# HIVE_SIGHT_MISC.net
KiCad netlist of a schematic drawn in Altium Designer
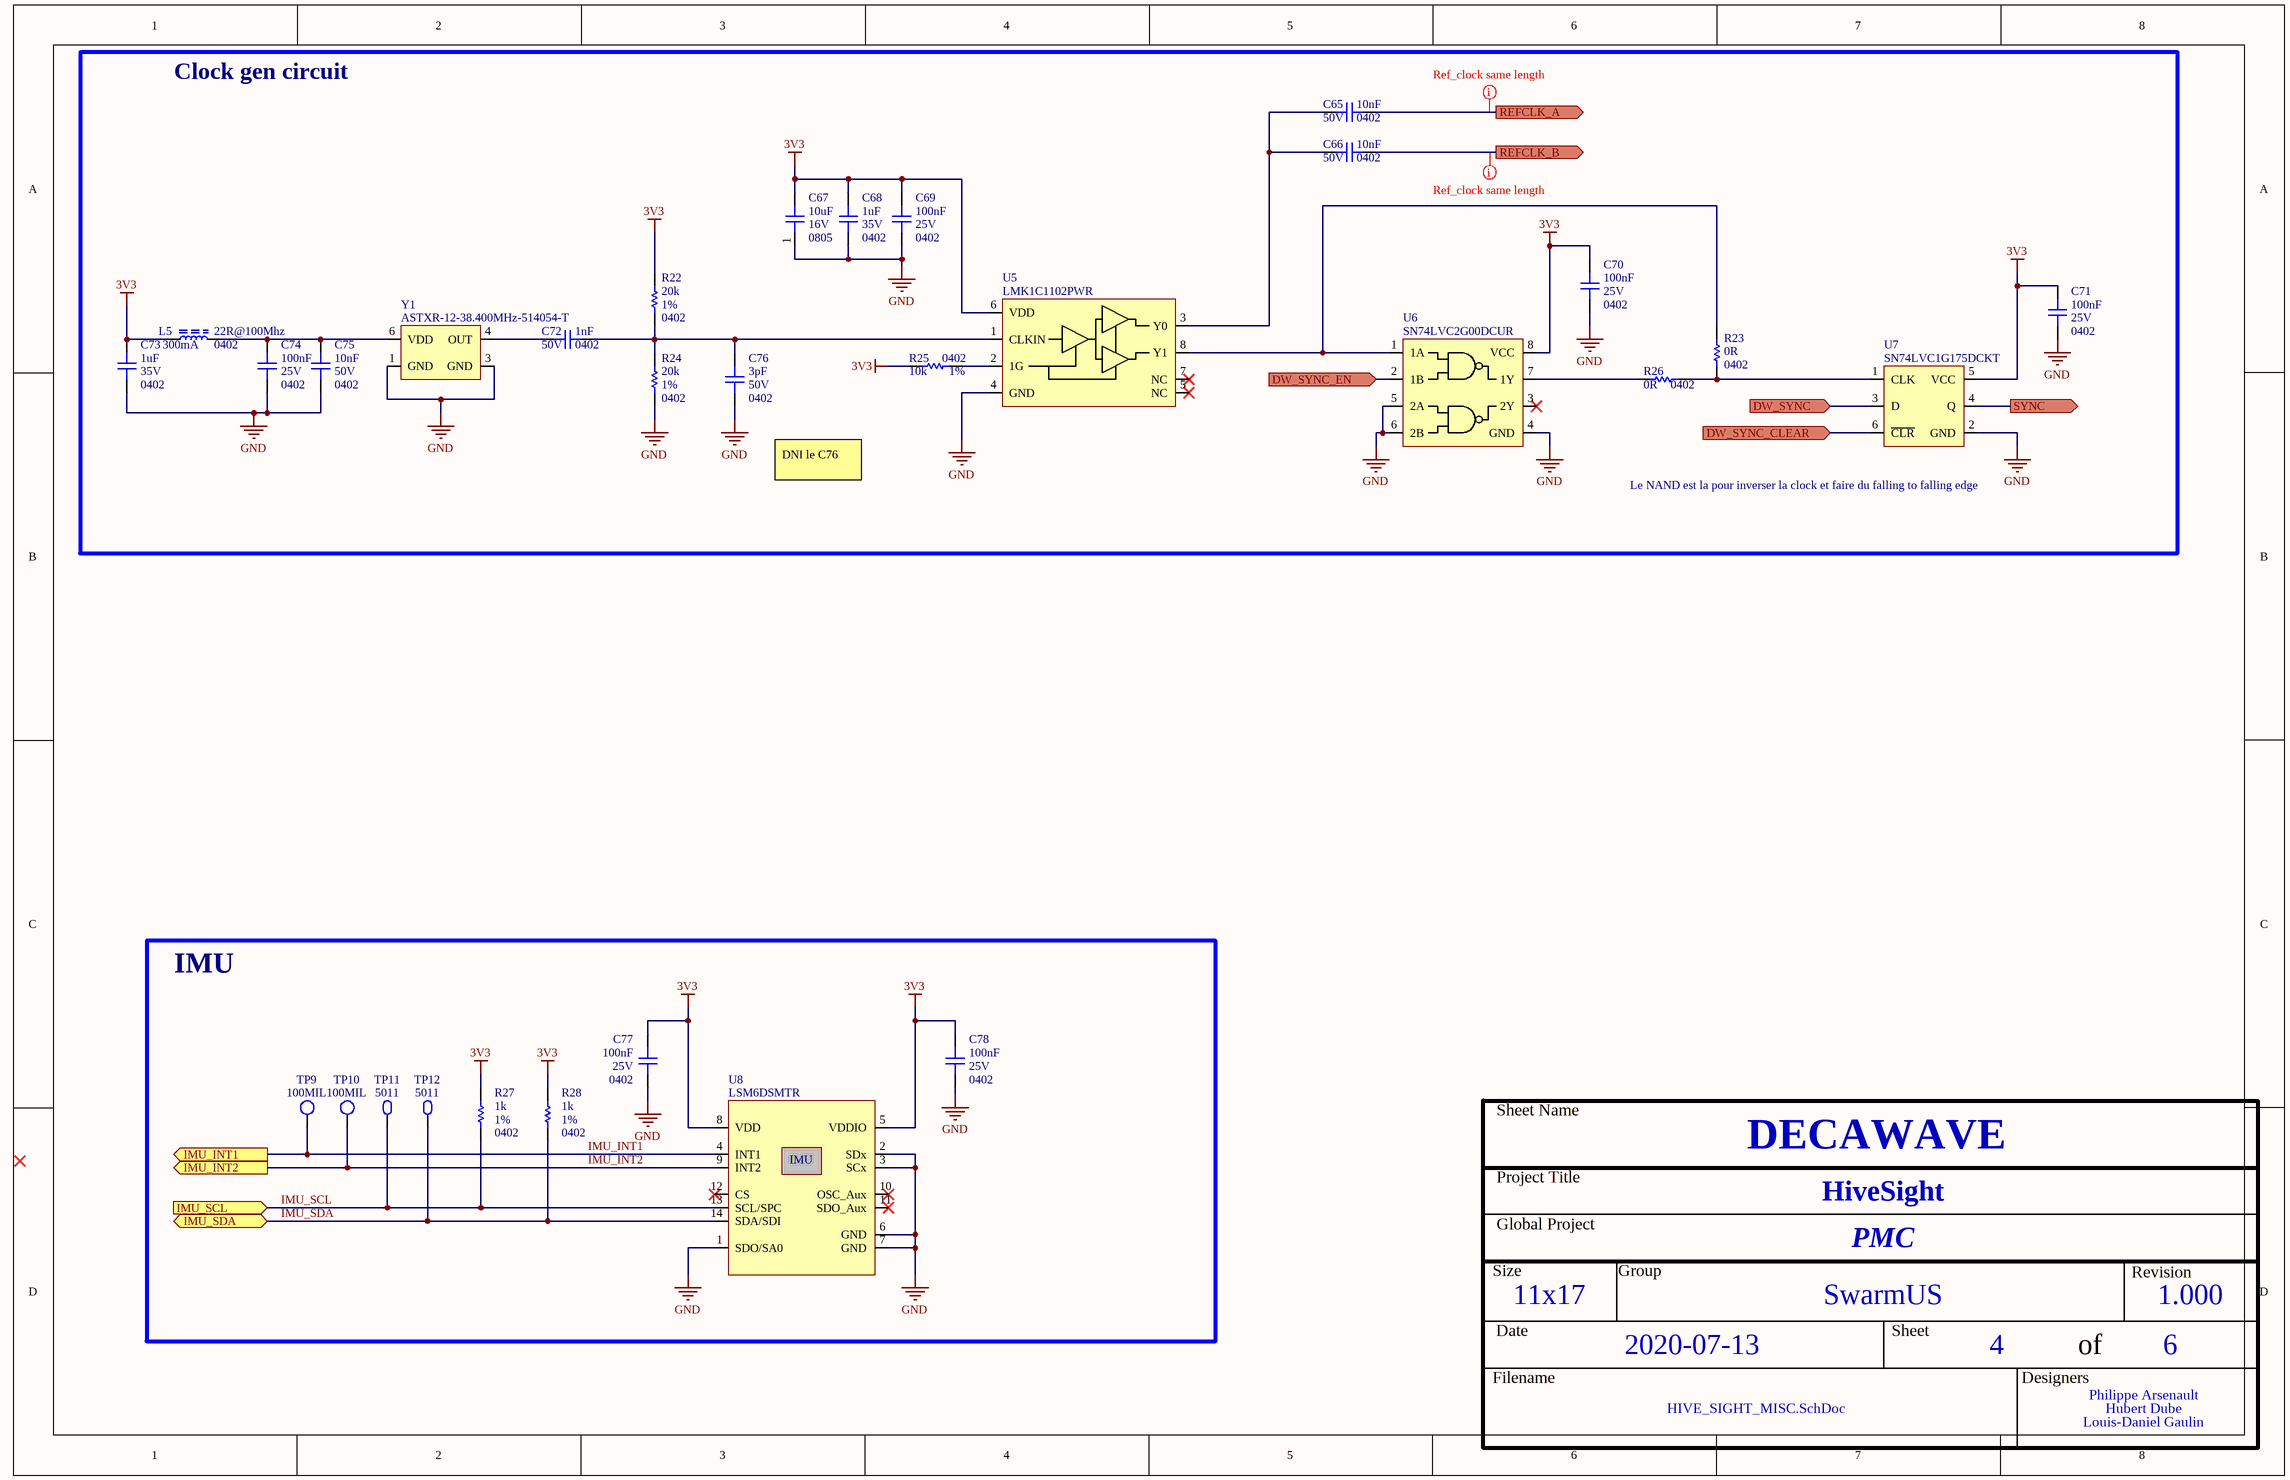
[diagram p0: HIVE_SIGHT_MISC.SchDoc]

(export (version "E")
  (design (tool "Eeschema 10.0.6"))
  (components
    (comp (ref "C65")
      (value "10nF")
      (footprint "GRAMS_MASTER_LIB_PCB:CAP_CER_0402")
      (description "CAP - CER 10nF ±10% 50V X7R - 0402")
      (fields
        (field (name "TOLERANCE") "10%")
        (field (name "PACKAGE") "0402")
        (field (name "VOLTAGE RATING") "50V")
        (field (name "Comment") "CL05B103KB5NFNC")
        (field (name "CREATEDBY/DATE") "Keven Deslandes - 2018/11/20")
        (field (name "VERIFIEDBY") "Nicolas Roy - 2018/12/11")
      )
      (libsource (lib "GRAMS_MASTER_LIB_SCH") (part "CAP_CER_CL05B103KB5NFNC"))
    )
    (comp (ref "C66")
      (value "10nF")
      (footprint "GRAMS_MASTER_LIB_PCB:CAP_CER_0402")
      (description "CAP - CER 10nF ±10% 50V X7R - 0402")
      (fields
        (field (name "TOLERANCE") "10%")
        (field (name "PACKAGE") "0402")
        (field (name "VOLTAGE RATING") "50V")
        (field (name "Comment") "CL05B103KB5NFNC")
        (field (name "CREATEDBY/DATE") "Keven Deslandes - 2018/11/20")
        (field (name "VERIFIEDBY") "Nicolas Roy - 2018/12/11")
      )
      (libsource (lib "GRAMS_MASTER_LIB_SCH") (part "CAP_CER_CL05B103KB5NFNC"))
    )
    (comp (ref "C67")
      (value "10uF")
      (footprint "CAP_CER_0805")
      (description "CAP - CER 10UF 10% 16V X5R - 0805")
      (fields
        (field (name "TOLERANCE") "10%")
        (field (name "PACKAGE") "0805")
        (field (name "VOLTAGE RATING") "16V")
        (field (name "Comment") "GRM21BR61C106KE15K")
        (field (name "CREATEDBY/DATE") "Caroline Paulin / 8 août 2018")
        (field (name "VERIFIEDBY") "Nicolas V. (2019-01-22)")
      )
      (libsource (lib "GRAMS_MASTER_LIB") (part "CAP_CER_GRM21BR61C106KE15K"))
    )
    (comp (ref "C68")
      (value "1uF")
      (footprint "GRAMS_MASTER_LIB_PCB:CAP_CER_0402")
      (description "CAP - CER 1uF 10% 35V X5R - 0402")
      (fields
        (field (name "TOLERANCE") "10%")
        (field (name "PACKAGE") "0402")
        (field (name "VOLTAGE RATING") "35V")
        (field (name "Comment") "CL05A105KL5NRNC")
        (field (name "CREATEDBY/DATE") "Nicolas Roy 2018-10-03")
        (field (name "VERIFIEDBY") "Caroline Paulin - 18 janv 2019")
      )
      (libsource (lib "GRAMS_MASTER_LIB_SCH") (part "CAP_CER_CL05A105KL5NRNC"))
    )
    (comp (ref "C69")
      (value "100nF")
      (footprint "GRAMS_MASTER_LIB_PCB:CAP_CER_0402")
      (description "CAP - CER 0.1µF 10% 25V X7R - 0402")
      (fields
        (field (name "TOLERANCE") "10%")
        (field (name "PACKAGE") "0402")
        (field (name "VOLTAGE RATING") "25V")
        (field (name "Comment") "CGA2B3X7R1E104K050BB")
        (field (name "CREATEDBY/DATE") "Nicolas Roy 2018-11-07")
        (field (name "VERIFIEDBY") "Nicolas V. (2019-01-22)")
      )
      (libsource (lib "GRAMS_MASTER_LIB_SCH") (part "CAP_CER_CGA2B3X7R1E104K050BB"))
    )
    (comp (ref "C70")
      (value "100nF")
      (footprint "GRAMS_MASTER_LIB_PCB:CAP_CER_0402")
      (description "CAP - CER 0.1µF 10% 25V X7R - 0402")
      (fields
        (field (name "TOLERANCE") "10%")
        (field (name "PACKAGE") "0402")
        (field (name "VOLTAGE RATING") "25V")
        (field (name "Comment") "CGA2B3X7R1E104K050BB")
        (field (name "CREATEDBY/DATE") "Nicolas Roy 2018-11-07")
        (field (name "VERIFIEDBY") "Nicolas V. (2019-01-22)")
      )
      (libsource (lib "GRAMS_MASTER_LIB_SCH") (part "CAP_CER_CGA2B3X7R1E104K050BB"))
    )
    (comp (ref "C71")
      (value "100nF")
      (footprint "GRAMS_MASTER_LIB_PCB:CAP_CER_0402")
      (description "CAP - CER 0.1µF 10% 25V X7R - 0402")
      (fields
        (field (name "TOLERANCE") "10%")
        (field (name "PACKAGE") "0402")
        (field (name "VOLTAGE RATING") "25V")
        (field (name "Comment") "CGA2B3X7R1E104K050BB")
        (field (name "CREATEDBY/DATE") "Nicolas Roy 2018-11-07")
        (field (name "VERIFIEDBY") "Nicolas V. (2019-01-22)")
      )
      (libsource (lib "GRAMS_MASTER_LIB_SCH") (part "CAP_CER_CGA2B3X7R1E104K050BB"))
    )
    (comp (ref "C72")
      (value "1nF")
      (footprint "CAP_CER_0402")
      (description "CAP - CER 1nF 10% 50V X7R - 0402")
      (fields
        (field (name "TOLERANCE") "10%")
        (field (name "PACKAGE") "0402")
        (field (name "VOLTAGE RATING") "50V")
        (field (name "Comment") "CC0402KRX7R9BB102")
        (field (name "CREATEDBY/DATE") "Jonathan Bouchard 2019-04-06")
        (field (name "VERIFIEDBY") "Nicolas V. (2019-04-30)")
      )
      (libsource (lib "GRAMS_MASTER_LIB_SCH") (part "CAP_CER_CC0402KRX7R9BB102"))
    )
    (comp (ref "C73")
      (value "1uF")
      (footprint "GRAMS_MASTER_LIB_PCB:CAP_CER_0402")
      (description "CAP - CER 1uF 10% 35V X5R - 0402")
      (fields
        (field (name "TOLERANCE") "10%")
        (field (name "PACKAGE") "0402")
        (field (name "VOLTAGE RATING") "35V")
        (field (name "Comment") "CL05A105KL5NRNC")
        (field (name "CREATEDBY/DATE") "Nicolas Roy 2018-10-03")
        (field (name "VERIFIEDBY") "Caroline Paulin - 18 janv 2019")
      )
      (libsource (lib "GRAMS_MASTER_LIB_SCH") (part "CAP_CER_CL05A105KL5NRNC"))
    )
    (comp (ref "C74")
      (value "100nF")
      (footprint "GRAMS_MASTER_LIB_PCB:CAP_CER_0402")
      (description "CAP - CER 0.1µF 10% 25V X7R - 0402")
      (fields
        (field (name "TOLERANCE") "10%")
        (field (name "PACKAGE") "0402")
        (field (name "VOLTAGE RATING") "25V")
        (field (name "Comment") "CGA2B3X7R1E104K050BB")
        (field (name "CREATEDBY/DATE") "Nicolas Roy 2018-11-07")
        (field (name "VERIFIEDBY") "Nicolas V. (2019-01-22)")
      )
      (libsource (lib "GRAMS_MASTER_LIB_SCH") (part "CAP_CER_CGA2B3X7R1E104K050BB"))
    )
    (comp (ref "C75")
      (value "10nF")
      (footprint "GRAMS_MASTER_LIB_PCB:CAP_CER_0402")
      (description "CAP - CER 10nF ±10% 50V X7R - 0402")
      (fields
        (field (name "TOLERANCE") "10%")
        (field (name "PACKAGE") "0402")
        (field (name "VOLTAGE RATING") "50V")
        (field (name "Comment") "CL05B103KB5NFNC")
        (field (name "CREATEDBY/DATE") "Keven Deslandes - 2018/11/20")
        (field (name "VERIFIEDBY") "Nicolas Roy - 2018/12/11")
      )
      (libsource (lib "GRAMS_MASTER_LIB_SCH") (part "CAP_CER_CL05B103KB5NFNC"))
    )
    (comp (ref "C76")
      (value "3pF")
      (footprint "CAP_CER_0402")
      (description "CAP - CER 3pF 50V ±0.25pF C0G, NP0 - 0402")
      (fields
        (field (name "TOLERANCE") "±0.25pF")
        (field (name "PACKAGE") "0402")
        (field (name "VOLTAGE RATING") "50V")
        (field (name "Comment") "CC0402CRNPO9BN3R0")
        (field (name "CREATEDBY/DATE") "Philippe Arsenault/ 2020-07-24")
        (field (name "VERIFIEDBY") "Louis-Daniel Gaulin / 2020-07-29")
      )
      (libsource (lib "SWARMUS_LIB") (part "CAP_CER_CC0402CRNPO9BN3R0"))
    )
    (comp (ref "C77")
      (value "100nF")
      (footprint "GRAMS_MASTER_LIB_PCB:CAP_CER_0402")
      (description "CAP - CER 0.1µF 10% 25V X7R - 0402")
      (fields
        (field (name "TOLERANCE") "10%")
        (field (name "PACKAGE") "0402")
        (field (name "VOLTAGE RATING") "25V")
        (field (name "Comment") "CGA2B3X7R1E104K050BB")
        (field (name "CREATEDBY/DATE") "Nicolas Roy 2018-11-07")
        (field (name "VERIFIEDBY") "Nicolas V. (2019-01-22)")
      )
      (libsource (lib "GRAMS_MASTER_LIB_SCH") (part "CAP_CER_CGA2B3X7R1E104K050BB"))
    )
    (comp (ref "C78")
      (value "100nF")
      (footprint "GRAMS_MASTER_LIB_PCB:CAP_CER_0402")
      (description "CAP - CER 0.1µF 10% 25V X7R - 0402")
      (fields
        (field (name "TOLERANCE") "10%")
        (field (name "PACKAGE") "0402")
        (field (name "VOLTAGE RATING") "25V")
        (field (name "Comment") "CGA2B3X7R1E104K050BB")
        (field (name "CREATEDBY/DATE") "Nicolas Roy 2018-11-07")
        (field (name "VERIFIEDBY") "Nicolas V. (2019-01-22)")
      )
      (libsource (lib "GRAMS_MASTER_LIB_SCH") (part "CAP_CER_CGA2B3X7R1E104K050BB"))
    )
    (comp (ref "L5")
      (value "22R@100Mhz")
      (footprint "FER_0402")
      (description "FER - FERRITE BEAD 22 OHM - 0402")
      (fields
        (field (name "CURRENT RATING") "300mA")
        (field (name "PACKAGE") "0402")
        (field (name "Comment") "BLM15BB220SN1D")
        (field (name "CREATEDBY/DATE") "Philippe Arsenault/2020-11-03")
      )
      (libsource (lib "a_Valider_PA") (part "FER_BLM15BB220SN1D"))
    )
    (comp (ref "R22")
      (value "20k")
      (footprint "GRAMS_MASTER_LIB_PCB:RES_0402")
      (description "RES - 20K 1% 1/16W  - 0402")
      (fields
        (field (name "TOLERANCE") "1%")
        (field (name "PACKAGE") "0402")
        (field (name "Comment") "RC0402FR-0720KL")
        (field (name "CREATEDBY/DATE") "Keven Deslandes 2018-10-18")
        (field (name "VERIFIEDBY") "Caroline Paulin - 7 janv 2019")
      )
      (libsource (lib "GRAMS_MASTER_LIB_SCH") (part "RES_RC0402FR-0720KL"))
    )
    (comp (ref "R23")
      (value "0R")
      (footprint "RES_0402")
      (description "RES - 0R 1/16W 1A  - 0402")
      (fields
        (field (name "PACKAGE") "0402")
        (field (name "Comment") "RC0402FR-070RL")
        (field (name "CREATEDBY/DATE") "Keven Deslandes 2018-09-12")
        (field (name "VERIFIEDBY") "Caroline Paulin - 27 fév 2019")
      )
      (libsource (lib "GRAMS_MASTER_LIB") (part "RES_RC0402FR-070RL"))
    )
    (comp (ref "R24")
      (value "20k")
      (footprint "GRAMS_MASTER_LIB_PCB:RES_0402")
      (description "RES - 20K 1% 1/16W  - 0402")
      (fields
        (field (name "TOLERANCE") "1%")
        (field (name "PACKAGE") "0402")
        (field (name "Comment") "RC0402FR-0720KL")
        (field (name "CREATEDBY/DATE") "Keven Deslandes 2018-10-18")
        (field (name "VERIFIEDBY") "Caroline Paulin - 7 janv 2019")
      )
      (libsource (lib "GRAMS_MASTER_LIB_SCH") (part "RES_RC0402FR-0720KL"))
    )
    (comp (ref "R25")
      (value "10k")
      (footprint "GRAMS_MASTER_LIB_PCB:RES_0402")
      (description "RES - 10K OHMS 1% 1/16W - 0402")
      (fields
        (field (name "TOLERANCE") "1%")
        (field (name "PACKAGE") "0402")
        (field (name "Comment") "RC0402FR-0710KL")
        (field (name "CREATEDBY/DATE") "Nicolas V. (2018-11-20)")
        (field (name "VERIFIEDBY") "Nicolas V. (2018-11-20)")
      )
      (libsource (lib "GRAMS_MASTER_LIB_SCH") (part "RES_RC0402FR-0710KL"))
    )
    (comp (ref "R26")
      (value "0R")
      (footprint "RES_0402")
      (description "RES - 0R 1/16W 1A  - 0402")
      (fields
        (field (name "PACKAGE") "0402")
        (field (name "Comment") "RC0402FR-070RL")
        (field (name "CREATEDBY/DATE") "Keven Deslandes 2018-09-12")
        (field (name "VERIFIEDBY") "Caroline Paulin - 27 fév 2019")
      )
      (libsource (lib "GRAMS_MASTER_LIB") (part "RES_RC0402FR-070RL"))
    )
    (comp (ref "R27")
      (value "1k")
      (footprint "GRAMS_MASTER_LIB_PCB:RES_0402")
      (description "RES - 1K OHM 1% 1/16W - 0402")
      (fields
        (field (name "TOLERANCE") "1%")
        (field (name "PACKAGE") "0402")
        (field (name "Comment") "RC0402FR-071KL")
        (field (name "CREATEDBY/DATE") "Jonathan Bouchard 2018-07-05")
        (field (name "VERIFIEDBY") "Arnaud Samson 16-07-18")
      )
      (libsource (lib "GRAMS_MASTER_LIB_SCH") (part "RES_RC0402FR-071KL"))
    )
    (comp (ref "R28")
      (value "1k")
      (footprint "GRAMS_MASTER_LIB_PCB:RES_0402")
      (description "RES - 1K OHM 1% 1/16W - 0402")
      (fields
        (field (name "TOLERANCE") "1%")
        (field (name "PACKAGE") "0402")
        (field (name "Comment") "RC0402FR-071KL")
        (field (name "CREATEDBY/DATE") "Jonathan Bouchard 2018-07-05")
        (field (name "VERIFIEDBY") "Arnaud Samson 16-07-18")
      )
      (libsource (lib "GRAMS_MASTER_LIB_SCH") (part "RES_RC0402FR-071KL"))
    )
    (comp (ref "TP9")
      (value "100MIL")
      (footprint "grams_master_lib_pcb:TPO_TH_ROUND_100MIL")
      (description "TPO - TEST POINT ROUND TH  - 100MIL")
      (fields
        (field (name "CREATEDBY/DATE") "Louis-Daniel Gaulin/ 14/01/2020")
        (field (name "VERIFIEDBY") "C.Paulin - 21/01/2020")
      )
      (libsource (lib "GRAMS_MASTER_LIB_SCH") (part "TPO_TH_ROUND_100MIL"))
    )
    (comp (ref "TP10")
      (value "100MIL")
      (footprint "grams_master_lib_pcb:TPO_TH_ROUND_100MIL")
      (description "TPO - TEST POINT ROUND TH  - 100MIL")
      (fields
        (field (name "CREATEDBY/DATE") "Louis-Daniel Gaulin/ 14/01/2020")
        (field (name "VERIFIEDBY") "C.Paulin - 21/01/2020")
      )
      (libsource (lib "GRAMS_MASTER_LIB_SCH") (part "TPO_TH_ROUND_100MIL"))
    )
    (comp (ref "TP11")
      (value "5011")
      (footprint "TPO_5011")
      (description "TPO - TEST POINT - TH")
      (fields
        (field (name "CREATEDBY/DATE") "Louis-Daniel Gauli / 02-11-2020")
        (field (name "VERIFIEDBY") "Philippe Arsenault/2020-11-06")
      )
      (libsource (lib "SWARMUS_LIB") (part "TPO_5011"))
    )
    (comp (ref "TP12")
      (value "5011")
      (footprint "TPO_5011")
      (description "TPO - TEST POINT - TH")
      (fields
        (field (name "CREATEDBY/DATE") "Louis-Daniel Gauli / 02-11-2020")
        (field (name "VERIFIEDBY") "Philippe Arsenault/2020-11-06")
      )
      (libsource (lib "SWARMUS_LIB") (part "TPO_5011"))
    )
    (comp (ref "U5")
      (value "LMK1C1102PWR")
      (footprint "COM_BUF_LMK1C1102PWR")
      (description "COM - BUF - Clock buffer 3V3, 2V5, 1V8 2 Channel - TSSOP 8")
      (fields
        (field (name "CREATEDBY/DATE") "Philippe Arsenault/20-07-2020")
        (field (name "VERIFIEDBY") "Louis-Daniel Gaulin / 23-07-2020")
      )
      (libsource (lib "SWARMUS_LIB") (part "COM_BUF_LMK1C1102PWR"))
    )
    (comp (ref "U6")
      (value "SN74LVC2G00DCUR")
      (footprint "LOG_NAND_SN74LVC2G00DCUR")
      (description "LOG_NAND - GATE NAND 2CH 2-INP - 8-VSSOP")
      (fields
        (field (name "CREATEDBY/DATE") "Philippe Arsenault/21-07-2020")
        (field (name "VERIFIEDBY") "Louis-Daniel Gaulin / 23-07-2020")
      )
      (libsource (lib "SWARMUS_LIB") (part "LOG_NAND_SN74LVC2G00DCUR"))
    )
    (comp (ref "U7")
      (value "SN74LVC1G175DCKT")
      (footprint "LOG_FLIPFLOP_SN74LVC1G175DCKT")
      (description "LOG_FLIPFLOP - Single D flip-flop with Asynchronous clear - SOT-363")
      (fields
        (field (name "CREATEDBY/DATE") "Philippe Arsenault/21-07-2020")
        (field (name "VERIFIEDBY") "Louis-Daniel Gaulin / 03-10-2020")
      )
      (libsource (lib "SWARMUS_LIB") (part "LOG_FLIPFLOP_SN74LVC1G175DCKT"))
    )
    (comp (ref "U8")
      (value "LSM6DSMTR")
      (footprint "SEN_IMU_LSM6DSMTR")
      (description "SEN_IMU -  ACCEL/GYRO 6 Axis I2C/SPI - 14-VFLGA")
      (fields
        (field (name "CREATEDBY/DATE") "Louis-Daniel Gaulin / 06-10-2020")
        (field (name "VERIFIEDBY") "Philippe Arsenault/2020-11-06")
      )
      (libsource (lib "SWARMUS_LIB") (part "SEN_IMU_LSM6DSMTR"))
    )
    (comp (ref "Y1")
      (value "ASTXR-12-38.400MHz-514054-T")
      (footprint "OSC_ASTXR-12-38.400MHZ-514054-T")
      (fields
        (field (name "CREATEDBY/DATE") "Philippe Arsenault/18-07-2020")
        (field (name "VERIFIEDBY") "Louis-Daniel Gaulin / 03-10-2020")
      )
      (libsource (lib "SWARMUS_LIB") (part "OSC_ASTXR-12-38.400MHz-514054-T"))
    )
  )
  (nets
    (net (code "1") (name "/DW_SYNC") (class "Default")
      (node (ref "U7") (pin "3") (pinfunction "D_3") (pintype "passive"))
    )
    (net (code "2") (name "/DW_SYNC_CLEAR") (class "Default")
      (node (ref "U7") (pin "6") (pinfunction "CLR_6") (pintype "passive"))
    )
    (net (code "3") (name "/DW_SYNC_EN") (class "Default")
      (node (ref "U6") (pin "2") (pinfunction "1B_2") (pintype "passive"))
    )
    (net (code "4") (name "/IMU_INT1") (class "Default")
      (node (ref "TP9") (pin "1") (pinfunction "1_1") (pintype "passive"))
      (node (ref "U8") (pin "4") (pinfunction "INT1_4") (pintype "passive"))
    )
    (net (code "5") (name "/IMU_INT2") (class "Default")
      (node (ref "TP10") (pin "1") (pinfunction "1_1") (pintype "passive"))
      (node (ref "U8") (pin "9") (pinfunction "INT2_9") (pintype "passive"))
    )
    (net (code "6") (name "/IMU_SCL") (class "Default")
      (node (ref "R27") (pin "2") (pinfunction "2_2") (pintype "passive"))
      (node (ref "TP11") (pin "1") (pinfunction "1_1") (pintype "passive"))
      (node (ref "U8") (pin "13") (pinfunction "SCL/SPC_13") (pintype "passive"))
    )
    (net (code "7") (name "/IMU_SDA") (class "Default")
      (node (ref "R28") (pin "2") (pinfunction "2_2") (pintype "passive"))
      (node (ref "TP12") (pin "1") (pinfunction "1_1") (pintype "passive"))
      (node (ref "U8") (pin "14") (pinfunction "SDA/SDI_14") (pintype "passive"))
    )
    (net (code "8") (name "/REFCLK_A") (class "Default")
      (node (ref "C65") (pin "1") (pinfunction "1_1") (pintype "passive"))
    )
    (net (code "9") (name "/REFCLK_B") (class "Default")
      (node (ref "C66") (pin "1") (pinfunction "1_1") (pintype "passive"))
    )
    (net (code "10") (name "/SYNC") (class "Default")
      (node (ref "U7") (pin "4") (pinfunction "Q_4") (pintype "passive"))
    )
    (net (code "11") (name "3V3") (class "Default")
      (node (ref "C67") (pin "2") (pinfunction "2_2") (pintype "passive"))
      (node (ref "C68") (pin "2") (pinfunction "2_2") (pintype "passive"))
      (node (ref "C69") (pin "2") (pinfunction "2_2") (pintype "passive"))
      (node (ref "C70") (pin "2") (pinfunction "2_2") (pintype "passive"))
      (node (ref "C71") (pin "1") (pinfunction "1_1") (pintype "passive"))
      (node (ref "C73") (pin "2") (pinfunction "2_2") (pintype "passive"))
      (node (ref "C77") (pin "1") (pinfunction "1_1") (pintype "passive"))
      (node (ref "C78") (pin "1") (pinfunction "1_1") (pintype "passive"))
      (node (ref "L5") (pin "1") (pinfunction "1_1") (pintype "passive"))
      (node (ref "R22") (pin "2") (pinfunction "2_2") (pintype "passive"))
      (node (ref "R25") (pin "2") (pinfunction "2_2") (pintype "passive"))
      (node (ref "R27") (pin "1") (pinfunction "1_1") (pintype "passive"))
      (node (ref "R28") (pin "1") (pinfunction "1_1") (pintype "passive"))
      (node (ref "U5") (pin "6") (pinfunction "VDD_6") (pintype "passive"))
      (node (ref "U6") (pin "8") (pinfunction "VCC_8") (pintype "passive"))
      (node (ref "U7") (pin "5") (pinfunction "VCC_5") (pintype "passive"))
      (node (ref "U8") (pin "5") (pinfunction "VDDIO_5") (pintype "passive"))
      (node (ref "U8") (pin "8") (pinfunction "VDD_8") (pintype "passive"))
    )
    (net (code "12") (name "GND") (class "Default")
      (node (ref "C67") (pin "1") (pinfunction "1_1") (pintype "passive"))
      (node (ref "C68") (pin "1") (pinfunction "1_1") (pintype "passive"))
      (node (ref "C69") (pin "1") (pinfunction "1_1") (pintype "passive"))
      (node (ref "C70") (pin "1") (pinfunction "1_1") (pintype "passive"))
      (node (ref "C71") (pin "2") (pinfunction "2_2") (pintype "passive"))
      (node (ref "C73") (pin "1") (pinfunction "1_1") (pintype "passive"))
      (node (ref "C74") (pin "1") (pinfunction "1_1") (pintype "passive"))
      (node (ref "C75") (pin "1") (pinfunction "1_1") (pintype "passive"))
      (node (ref "C76") (pin "1") (pinfunction "1_1") (pintype "passive"))
      (node (ref "C77") (pin "2") (pinfunction "2_2") (pintype "passive"))
      (node (ref "C78") (pin "2") (pinfunction "2_2") (pintype "passive"))
      (node (ref "R24") (pin "1") (pinfunction "1_1") (pintype "passive"))
      (node (ref "U5") (pin "4") (pinfunction "GND_4") (pintype "passive"))
      (node (ref "U6") (pin "4") (pinfunction "GND_4") (pintype "passive"))
      (node (ref "U6") (pin "5") (pinfunction "2A_5") (pintype "passive"))
      (node (ref "U6") (pin "6") (pinfunction "2B_6") (pintype "passive"))
      (node (ref "U7") (pin "2") (pinfunction "GND_2") (pintype "passive"))
      (node (ref "U8") (pin "1") (pinfunction "SDO/SA0_1") (pintype "passive"))
      (node (ref "U8") (pin "2") (pinfunction "SDx_2") (pintype "passive"))
      (node (ref "U8") (pin "3") (pinfunction "SCx_3") (pintype "passive"))
      (node (ref "U8") (pin "6") (pinfunction "GND_6") (pintype "passive"))
      (node (ref "U8") (pin "7") (pinfunction "GND_7") (pintype "passive"))
      (node (ref "Y1") (pin "1") (pinfunction "GND_1") (pintype "passive"))
      (node (ref "Y1") (pin "3") (pinfunction "GND_3") (pintype "passive"))
    )
    (net (code "13") (name "Net-(U5-1G)") (class "Default")
      (node (ref "R25") (pin "1") (pinfunction "1_1") (pintype "passive"))
      (node (ref "U5") (pin "2") (pinfunction "1G_2") (pintype "passive"))
    )
    (net (code "14") (name "Net-(U5-CLKIN)") (class "Default")
      (node (ref "C72") (pin "1") (pinfunction "1_1") (pintype "passive"))
      (node (ref "C76") (pin "2") (pinfunction "2_2") (pintype "passive"))
      (node (ref "R22") (pin "1") (pinfunction "1_1") (pintype "passive"))
      (node (ref "R24") (pin "2") (pinfunction "2_2") (pintype "passive"))
      (node (ref "U5") (pin "1") (pinfunction "CLKIN_1") (pintype "passive"))
    )
    (net (code "15") (name "Net-(U5-Y0)") (class "Default")
      (node (ref "C65") (pin "2") (pinfunction "2_2") (pintype "passive"))
      (node (ref "C66") (pin "2") (pinfunction "2_2") (pintype "passive"))
      (node (ref "U5") (pin "3") (pinfunction "Y0_3") (pintype "passive"))
    )
    (net (code "16") (name "Net-(U5-Y1)") (class "Default")
      (node (ref "R23") (pin "2") (pinfunction "2_2") (pintype "passive"))
      (node (ref "U5") (pin "8") (pinfunction "Y1_8") (pintype "passive"))
      (node (ref "U6") (pin "1") (pinfunction "1A_1") (pintype "passive"))
    )
    (net (code "17") (name "Net-(U6-1Y)") (class "Default")
      (node (ref "R26") (pin "2") (pinfunction "2_2") (pintype "passive"))
      (node (ref "U6") (pin "7") (pinfunction "1Y_7") (pintype "passive"))
    )
    (net (code "18") (name "Net-(U7-CLK)") (class "Default")
      (node (ref "R23") (pin "1") (pinfunction "1_1") (pintype "passive"))
      (node (ref "R26") (pin "1") (pinfunction "1_1") (pintype "passive"))
      (node (ref "U7") (pin "1") (pinfunction "CLK_1") (pintype "passive"))
    )
    (net (code "19") (name "Net-(Y1-OUT)") (class "Default")
      (node (ref "C72") (pin "2") (pinfunction "2_2") (pintype "passive"))
      (node (ref "Y1") (pin "4") (pinfunction "OUT_4") (pintype "passive"))
    )
    (net (code "20") (name "Net-(Y1-VDD)") (class "Default")
      (node (ref "C74") (pin "2") (pinfunction "2_2") (pintype "passive"))
      (node (ref "C75") (pin "2") (pinfunction "2_2") (pintype "passive"))
      (node (ref "L5") (pin "2") (pinfunction "2_2") (pintype "passive"))
      (node (ref "Y1") (pin "6") (pinfunction "VDD_6") (pintype "passive"))
    )
    (net (code "21") (name "unconnected-(U5-NC-Pad5)") (class "Default")
      (node (ref "U5") (pin "5") (pinfunction "NC_5") (pintype "passive+no_connect"))
    )
    (net (code "22") (name "unconnected-(U5-NC-Pad7)") (class "Default")
      (node (ref "U5") (pin "7") (pinfunction "NC_7") (pintype "passive+no_connect"))
    )
    (net (code "23") (name "unconnected-(U6-2Y-Pad3)") (class "Default")
      (node (ref "U6") (pin "3") (pinfunction "2Y_3") (pintype "passive+no_connect"))
    )
    (net (code "24") (name "unconnected-(U8-CS-Pad12)") (class "Default")
      (node (ref "U8") (pin "12") (pinfunction "CS_12") (pintype "passive+no_connect"))
    )
    (net (code "25") (name "unconnected-(U8-OSC_Aux-Pad10)") (class "Default")
      (node (ref "U8") (pin "10") (pinfunction "OSC_Aux_10") (pintype "passive+no_connect"))
    )
    (net (code "26") (name "unconnected-(U8-SDO_Aux-Pad11)") (class "Default")
      (node (ref "U8") (pin "11") (pinfunction "SDO_Aux_11") (pintype "passive+no_connect"))
    )
  )
)
